# Power.net
KiCad netlist of a schematic drawn in Altium Designer
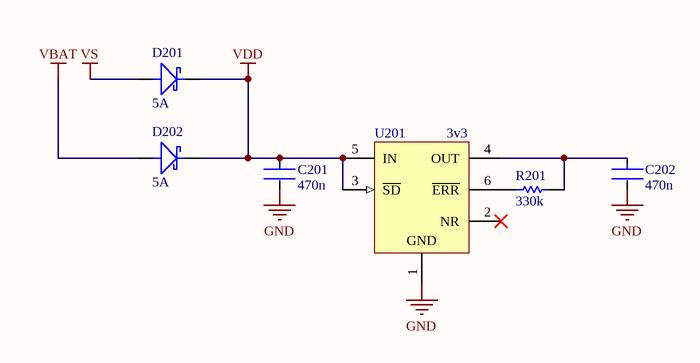
[diagram p0: Power.SchDoc]

(export (version "E")
  (design (tool "Eeschema 10.0.6"))
  (components
    (comp (ref "C201")
      (value "470n")
      (footprint "FP-GRT155-0_05-MFG")
      (description "Multi-Layer Ceramic Capacitor 470nF 25V X5R ±10% 0402 Paper T/R")
      (fields (field (name "TOLERANCE") "10%"))
      (libsource (lib "Main") (part "GRT155R61E474KE01D"))
    )
    (comp (ref "C202")
      (value "470n")
      (footprint "FP-GRT155-0_05-MFG")
      (description "Multi-Layer Ceramic Capacitor 470nF 25V X5R ±10% 0402 Paper T/R")
      (fields (field (name "TOLERANCE") "10%"))
      (libsource (lib "Main") (part "GRT155R61E474KE01D"))
    )
    (comp (ref "D201")
      (value "5A")
      (footprint "SODFL470X105-2L")
      (libsource (lib "Main") (part "RB080LAM-30TR"))
    )
    (comp (ref "D202")
      (value "5A")
      (footprint "SODFL470X105-2L")
      (libsource (lib "Main") (part "RB080LAM-30TR"))
    )
    (comp (ref "R201")
      (value "330k")
      (footprint "RESC1005X04N")
      (fields (field (name "MANUFACTURER") "Panasonic") (field (name "PART NUMBER") "ERJ2RKF27R0X"))
      (libsource (lib "Main") (part "ERJ-2GEJ334X"))
    )
    (comp (ref "U201")
      (value "3v3")
      (footprint "SOT95P280X145-6L")
      (fields (field (name "MANUFACTURER") "Analog Devices") (field (name "PARTNUMBER") "ADP3300ARTZ-3.3RL7"))
      (libsource (lib "Main") (part "ADP3300ARTZ-3.3RL7"))
    )
  )
  (nets
    (net (code "1") (name "GND") (class "Default")
      (node (ref "C201") (pin "2") (pinfunction "2_2") (pintype "passive"))
      (node (ref "C202") (pin "2") (pinfunction "2_2") (pintype "passive"))
      (node (ref "U201") (pin "1") (pinfunction "GND_1") (pintype "power_in"))
    )
    (net (code "2") (name "Net-(U201-OUT)") (class "Default")
      (node (ref "C202") (pin "1") (pinfunction "1_1") (pintype "passive"))
      (node (ref "R201") (pin "1") (pinfunction "1_1") (pintype "passive"))
      (node (ref "U201") (pin "4") (pinfunction "OUT_4") (pintype "power_in"))
    )
    (net (code "3") (name "Net-(U201-~{ERR})") (class "Default")
      (node (ref "R201") (pin "2") (pinfunction "2_2") (pintype "passive"))
      (node (ref "U201") (pin "6") (pinfunction "~{ERR}_6") (pintype "open_collector"))
    )
    (net (code "4") (name "VBAT") (class "Default")
      (node (ref "D202") (pin "2") (pinfunction "2_2") (pintype "power_in"))
    )
    (net (code "5") (name "VDD") (class "Default")
      (node (ref "C201") (pin "1") (pinfunction "1_1") (pintype "passive"))
      (node (ref "D201") (pin "1") (pinfunction "1_1") (pintype "power_in"))
      (node (ref "D202") (pin "1") (pinfunction "1_1") (pintype "power_in"))
      (node (ref "U201") (pin "3") (pinfunction "~{SD}_3") (pintype "input"))
      (node (ref "U201") (pin "5") (pinfunction "IN_5") (pintype "power_in"))
    )
    (net (code "6") (name "VS") (class "Default")
      (node (ref "D201") (pin "2") (pinfunction "2_2") (pintype "power_in"))
    )
    (net (code "7") (name "unconnected-(U201-NR-Pad2)") (class "Default")
      (node (ref "U201") (pin "2") (pinfunction "NR_2") (pintype "passive+no_connect"))
    )
  )
)
